# ra-chan.net
KiCad netlist of a schematic drawn in Altium Designer
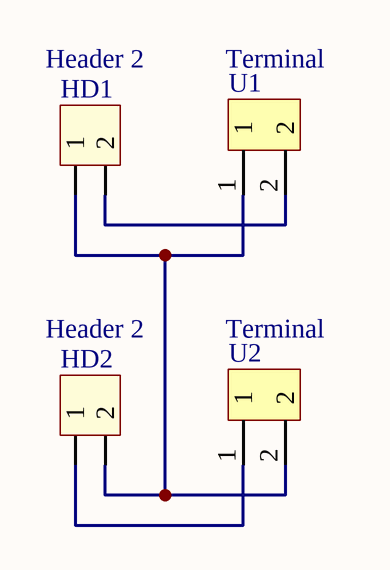
[diagram p0: ra-chan.SchDoc]

(export (version "E")
  (design (tool "Eeschema 10.0.6"))
  (components
    (comp (ref "HD1")
      (value "Header 2")
      (footprint "HED2")
      (description "Header 2 (Green)")
      (libsource (lib "syhaunguyen") (part "Hed2"))
    )
    (comp (ref "HD2")
      (value "Header 2")
      (footprint "HED2")
      (description "Header 2 (Green)")
      (libsource (lib "syhaunguyen") (part "Hed2"))
    )
    (comp (ref "U1")
      (value "Terminal")
      (footprint "Terminal 5.08")
      (libsource (lib "THU_VIEN_PQB") (part "TERMINAL5.08"))
    )
    (comp (ref "U2")
      (value "Terminal")
      (footprint "Terminal 5.08")
      (libsource (lib "THU_VIEN_PQB") (part "TERMINAL5.08"))
    )
  )
  (nets
    (net (code "1") (name "Net-(HD1-Pad1)") (class "Default")
      (node (ref "HD1") (pin "1") (pinfunction "1_1") (pintype "passive"))
      (node (ref "HD2") (pin "2") (pinfunction "2_2") (pintype "passive"))
      (node (ref "U1") (pin "1") (pinfunction "1_1") (pintype "passive"))
      (node (ref "U2") (pin "2") (pinfunction "2_2") (pintype "passive"))
    )
    (net (code "2") (name "Net-(HD1-Pad2)") (class "Default")
      (node (ref "HD1") (pin "2") (pinfunction "2_2") (pintype "passive"))
      (node (ref "U1") (pin "2") (pinfunction "2_2") (pintype "passive"))
    )
    (net (code "3") (name "Net-(HD2-Pad1)") (class "Default")
      (node (ref "HD2") (pin "1") (pinfunction "1_1") (pintype "passive"))
      (node (ref "U2") (pin "1") (pinfunction "1_1") (pintype "passive"))
    )
  )
)
